# DOIBoard3.net
KiCad netlist of a schematic drawn in Altium Designer
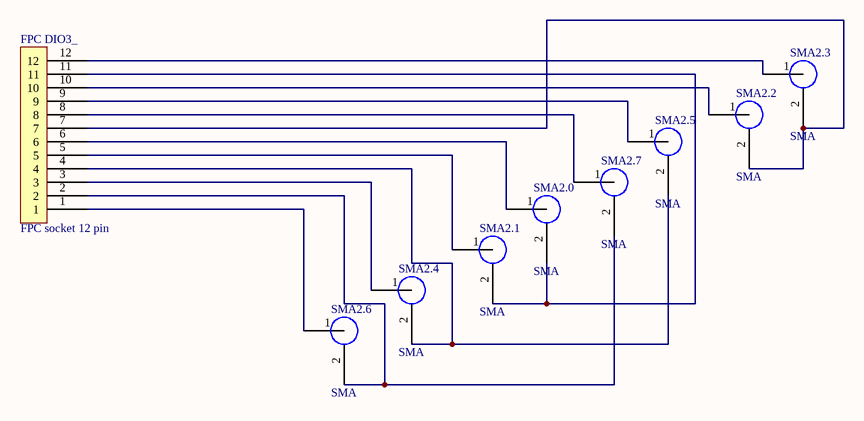
[diagram p0: DOIBoard3.SchDoc]

(export (version "E")
  (design (tool "Eeschema 10.0.6"))
  (components
    (comp (ref "FPC DIO3_")
      (value "FPC socket 12 pin")
      (footprint "FPC 12pin")
      (libsource (lib "Libaray") (part "FPC socket 12 pin"))
    )
    (comp (ref "SMA2.0") (value "SMA") (footprint "SMA") (libsource (lib "Libaray") (part "SMA")))
    (comp (ref "SMA2.1") (value "SMA") (footprint "SMA") (libsource (lib "Libaray") (part "SMA")))
    (comp (ref "SMA2.2") (value "SMA") (footprint "SMA") (libsource (lib "Libaray") (part "SMA")))
    (comp (ref "SMA2.3") (value "SMA") (footprint "SMA") (libsource (lib "Libaray") (part "SMA")))
    (comp (ref "SMA2.4") (value "SMA") (footprint "SMA") (libsource (lib "Libaray") (part "SMA")))
    (comp (ref "SMA2.5") (value "SMA") (footprint "SMA") (libsource (lib "Libaray") (part "SMA")))
    (comp (ref "SMA2.6") (value "SMA") (footprint "SMA") (libsource (lib "Libaray") (part "SMA")))
    (comp (ref "SMA2.7") (value "SMA") (footprint "SMA") (libsource (lib "Libaray") (part "SMA")))
  )
  (nets
    (net (code "1") (name "Net-(SMA2.0-Core)") (class "Default")
      (node (ref "FPC DIO3_") (pin "6") (pinfunction "6_6") (pintype "passive"))
      (node (ref "SMA2.0") (pin "1") (pinfunction "Core_1") (pintype "passive"))
    )
    (net (code "2") (name "Net-(SMA2.0-Ground)") (class "Default")
      (node (ref "FPC DIO3_") (pin "11") (pinfunction "11_11") (pintype "passive"))
      (node (ref "SMA2.0") (pin "2") (pinfunction "Ground_2") (pintype "passive"))
      (node (ref "SMA2.1") (pin "2") (pinfunction "Ground_2") (pintype "passive"))
    )
    (net (code "3") (name "Net-(SMA2.1-Core)") (class "Default")
      (node (ref "FPC DIO3_") (pin "5") (pinfunction "5_5") (pintype "passive"))
      (node (ref "SMA2.1") (pin "1") (pinfunction "Core_1") (pintype "passive"))
    )
    (net (code "4") (name "Net-(SMA2.2-Core)") (class "Default")
      (node (ref "FPC DIO3_") (pin "10") (pinfunction "10_10") (pintype "passive"))
      (node (ref "SMA2.2") (pin "1") (pinfunction "Core_1") (pintype "passive"))
    )
    (net (code "5") (name "Net-(SMA2.2-Ground)") (class "Default")
      (node (ref "FPC DIO3_") (pin "7") (pinfunction "7_7") (pintype "passive"))
      (node (ref "SMA2.2") (pin "2") (pinfunction "Ground_2") (pintype "passive"))
      (node (ref "SMA2.3") (pin "2") (pinfunction "Ground_2") (pintype "passive"))
    )
    (net (code "6") (name "Net-(SMA2.3-Core)") (class "Default")
      (node (ref "FPC DIO3_") (pin "12") (pinfunction "12_12") (pintype "passive"))
      (node (ref "SMA2.3") (pin "1") (pinfunction "Core_1") (pintype "passive"))
    )
    (net (code "7") (name "Net-(SMA2.4-Core)") (class "Default")
      (node (ref "FPC DIO3_") (pin "3") (pinfunction "3_3") (pintype "passive"))
      (node (ref "SMA2.4") (pin "1") (pinfunction "Core_1") (pintype "passive"))
    )
    (net (code "8") (name "Net-(SMA2.4-Ground)") (class "Default")
      (node (ref "FPC DIO3_") (pin "4") (pinfunction "4_4") (pintype "passive"))
      (node (ref "SMA2.4") (pin "2") (pinfunction "Ground_2") (pintype "passive"))
      (node (ref "SMA2.5") (pin "2") (pinfunction "Ground_2") (pintype "passive"))
    )
    (net (code "9") (name "Net-(SMA2.5-Core)") (class "Default")
      (node (ref "FPC DIO3_") (pin "9") (pinfunction "9_9") (pintype "passive"))
      (node (ref "SMA2.5") (pin "1") (pinfunction "Core_1") (pintype "passive"))
    )
    (net (code "10") (name "Net-(SMA2.6-Core)") (class "Default")
      (node (ref "FPC DIO3_") (pin "1") (pinfunction "1_1") (pintype "passive"))
      (node (ref "SMA2.6") (pin "1") (pinfunction "Core_1") (pintype "passive"))
    )
    (net (code "11") (name "Net-(SMA2.6-Ground)") (class "Default")
      (node (ref "FPC DIO3_") (pin "2") (pinfunction "2_2") (pintype "passive"))
      (node (ref "SMA2.6") (pin "2") (pinfunction "Ground_2") (pintype "passive"))
      (node (ref "SMA2.7") (pin "2") (pinfunction "Ground_2") (pintype "passive"))
    )
    (net (code "12") (name "Net-(SMA2.7-Core)") (class "Default")
      (node (ref "FPC DIO3_") (pin "8") (pinfunction "8_8") (pintype "passive"))
      (node (ref "SMA2.7") (pin "1") (pinfunction "Core_1") (pintype "passive"))
    )
  )
)
